# badge-inner1-revA.net
KiCad netlist of a schematic drawn in EAGLE
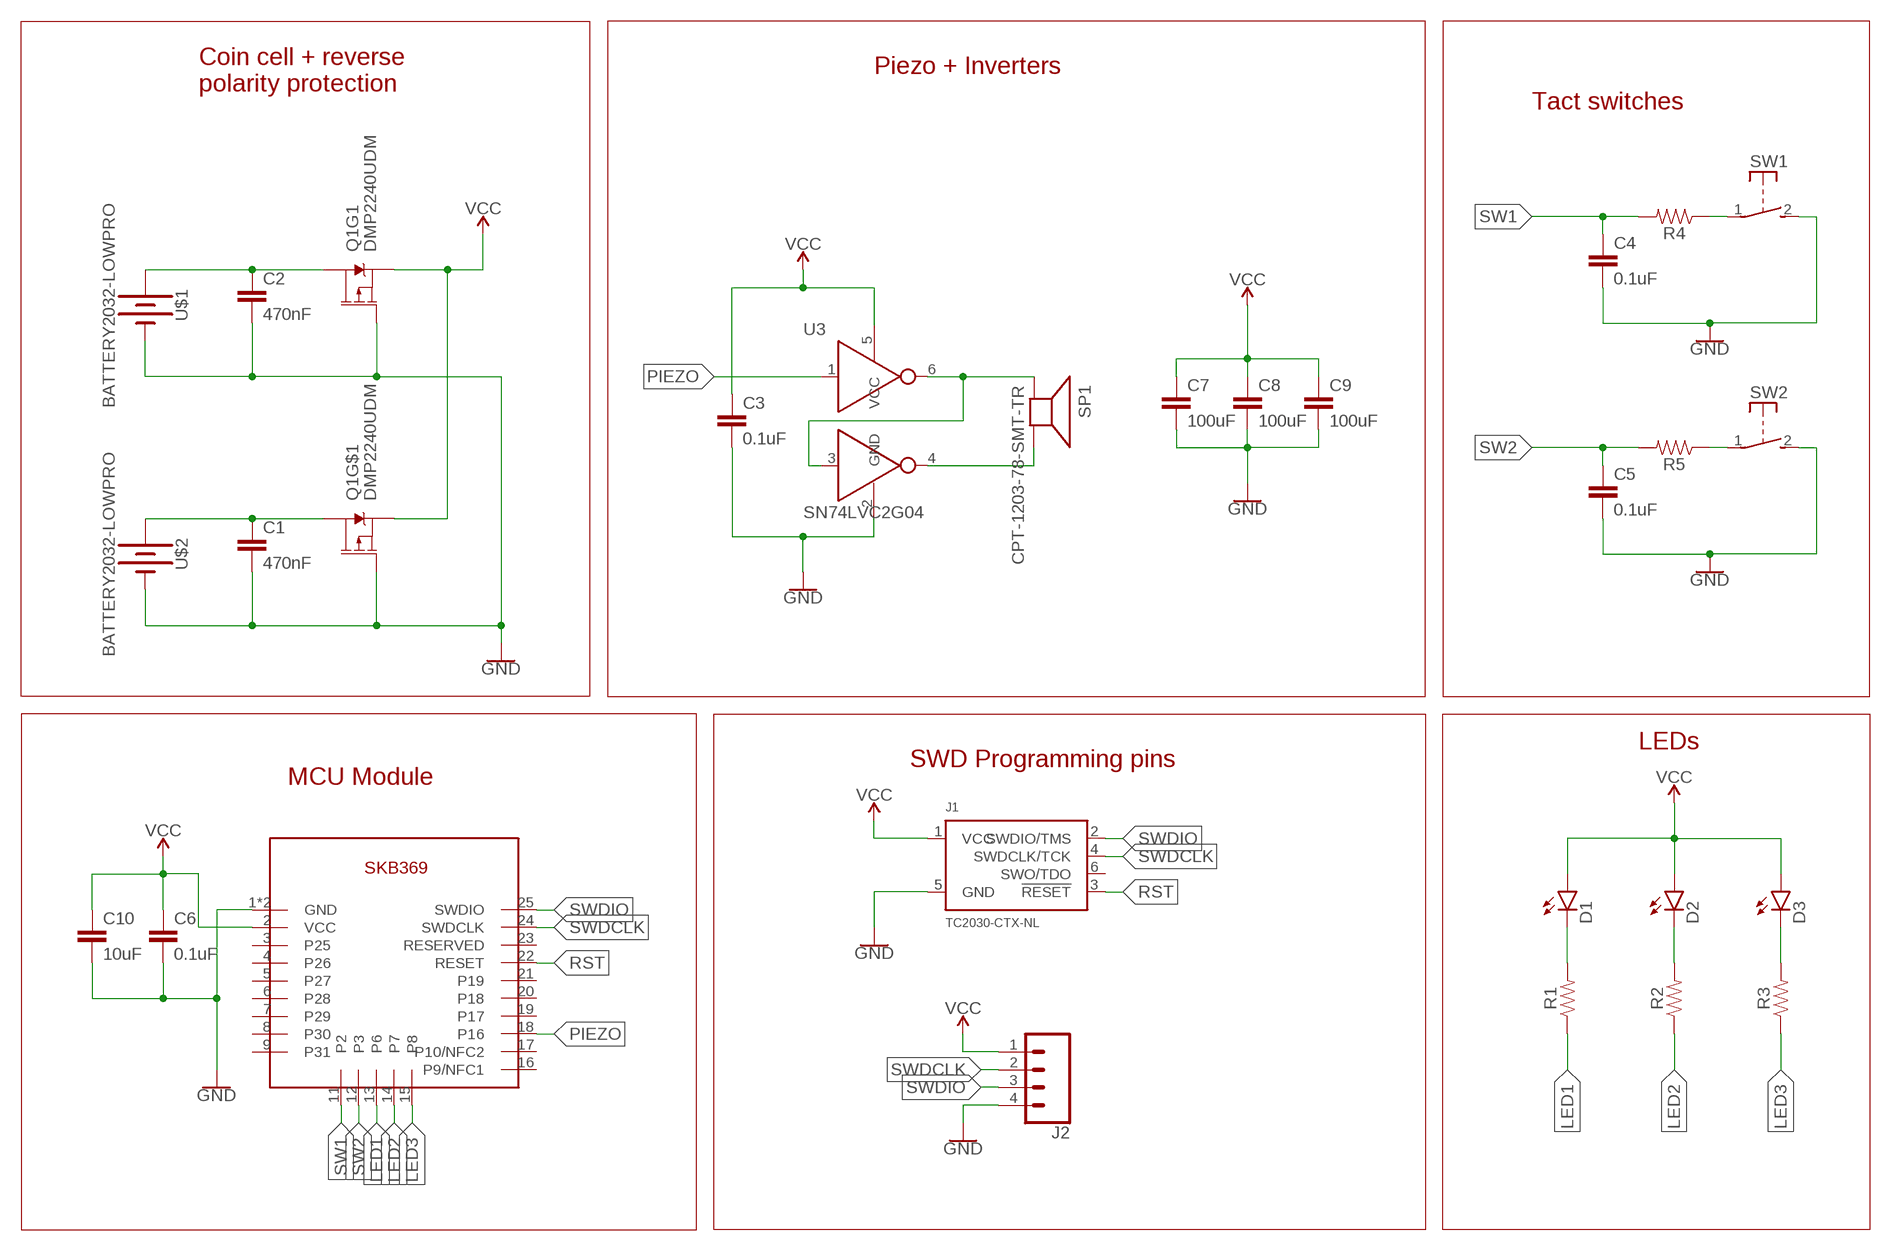
[diagram p0: schematic, sheet 1]

(export (version "E")
  (design (tool "Eeschema 10.0.6"))
  (components
    (comp (ref "C1")
      (value "470nF")
      (footprint "eagle-import:0603")
      (libsource (lib "eagle-import") (part "0.1UF-0603-25V-5%"))
    )
    (comp (ref "C2")
      (value "470nF")
      (footprint "eagle-import:0603")
      (libsource (lib "eagle-import") (part "0.1UF-0603-25V-5%"))
    )
    (comp (ref "C3")
      (value "0.1uF")
      (footprint "eagle-import:0603")
      (libsource (lib "eagle-import") (part "0.1UF-0603-25V-5%"))
    )
    (comp (ref "C4")
      (value "0.1uF")
      (footprint "eagle-import:0603")
      (libsource (lib "eagle-import") (part "0.1UF-0603-25V-5%"))
    )
    (comp (ref "C5")
      (value "0.1uF")
      (footprint "eagle-import:0603")
      (libsource (lib "eagle-import") (part "0.1UF-0603-25V-5%"))
    )
    (comp (ref "C6")
      (value "0.1uF")
      (footprint "eagle-import:0603")
      (libsource (lib "eagle-import") (part "0.1UF-0603-25V-5%"))
    )
    (comp (ref "C7")
      (value "100uF")
      (footprint "eagle-import:1206")
      (fields (field (name "SPICEPREFIX") "C"))
      (libsource (lib "eagle-import") (part "10UF-1206-6.3V-20%"))
    )
    (comp (ref "C8")
      (value "100uF")
      (footprint "eagle-import:1206")
      (fields (field (name "SPICEPREFIX") "C"))
      (libsource (lib "eagle-import") (part "10UF-1206-6.3V-20%"))
    )
    (comp (ref "C9")
      (value "100uF")
      (footprint "eagle-import:1206")
      (fields (field (name "SPICEPREFIX") "C"))
      (libsource (lib "eagle-import") (part "10UF-1206-6.3V-20%"))
    )
    (comp (ref "C10")
      (value "10uF")
      (footprint "eagle-import:0603")
      (libsource (lib "eagle-import") (part "0.1UF-0603-25V-5%"))
    )
    (comp (ref "D1")
      (value "SIDE-LED")
      (footprint "eagle-import:SIDE-LED")
      (libsource (lib "eagle-import") (part "SIDE-LED"))
    )
    (comp (ref "D2")
      (value "SIDE-LED")
      (footprint "eagle-import:SIDE-LED")
      (libsource (lib "eagle-import") (part "SIDE-LED"))
    )
    (comp (ref "D3")
      (value "SIDE-LED")
      (footprint "eagle-import:SIDE-LED")
      (libsource (lib "eagle-import") (part "SIDE-LED"))
    )
    (comp (ref "J1")
      (value "TC2030-CTX-NL")
      (footprint "eagle-import:TC2030-IDC-NL")
      (fields (field (name "MF") "Tag-Connect LLC") (field (name "MP") "TC2030-CTX"))
      (libsource (lib "eagle-import") (part "TC2030-CTX-NL"))
    )
    (comp (ref "J2")
      (value "CONN_04SMD_RA_FEMALE")
      (footprint "eagle-import:1X04_SMD_RA_FEMALE")
      (libsource (lib "eagle-import") (part "CONN_04SMD_RA_FEMALE"))
    )
    (comp (ref "Q1")
      (value "DMP2240UDM")
      (footprint "eagle-import:SOT26")
      (libsource (lib "eagle-import") (part "MOSFET_PCH_DUAL-DMP2240UDM"))
    )
    (comp (ref "R1")
      (value "0.05OHM-0603-1/5W-1%")
      (footprint "eagle-import:0603")
      (libsource (lib "eagle-import") (part "0.05OHM-0603-1/5W-1%"))
    )
    (comp (ref "R2")
      (value "0.05OHM-0603-1/5W-1%")
      (footprint "eagle-import:0603")
      (libsource (lib "eagle-import") (part "0.05OHM-0603-1/5W-1%"))
    )
    (comp (ref "R3")
      (value "0.05OHM-0603-1/5W-1%")
      (footprint "eagle-import:0603")
      (libsource (lib "eagle-import") (part "0.05OHM-0603-1/5W-1%"))
    )
    (comp (ref "R4")
      (value "0.05OHM-0603-1/5W-1%")
      (footprint "eagle-import:0603")
      (libsource (lib "eagle-import") (part "0.05OHM-0603-1/5W-1%"))
    )
    (comp (ref "R5")
      (value "0.05OHM-0603-1/5W-1%")
      (footprint "eagle-import:0603")
      (libsource (lib "eagle-import") (part "0.05OHM-0603-1/5W-1%"))
    )
    (comp (ref "SP1")
      (value "CPT-1203-78-SMT-TR")
      (footprint "eagle-import:CPT-1203-78-SMT-TR")
      (libsource (lib "eagle-import") (part "SPEAKER"))
    )
    (comp (ref "SW1")
      (value "EVQP4")
      (footprint "eagle-import:EVQP4KB")
      (libsource (lib "eagle-import") (part "EVQP4"))
    )
    (comp (ref "SW2")
      (value "EVQP4")
      (footprint "eagle-import:EVQP4KB")
      (libsource (lib "eagle-import") (part "EVQP4"))
    )
    (comp (ref "U$1")
      (value "BATTERY2032-LOWPRO")
      (footprint "eagle-import:COINCELL20LOWPRO")
      (libsource (lib "eagle-import") (part "BATTERY2032-LOWPRO"))
    )
    (comp (ref "U$2")
      (value "BATTERY2032-LOWPRO")
      (footprint "eagle-import:COINCELL20LOWPRO")
      (libsource (lib "eagle-import") (part "BATTERY2032-LOWPRO"))
    )
    (comp (ref "U1")
      (value "SKB369")
      (footprint "eagle-import:SKB369")
      (libsource (lib "eagle-import") (part "SKB369"))
    )
    (comp (ref "U3")
      (value "SN74LVC2G04")
      (footprint "eagle-import:SC70")
      (libsource (lib "eagle-import") (part "DUAL-INVERTERSN74LVC2G04"))
    )
  )
  (nets
    (net (code "1") (name "GND") (class "Default")
      (node (ref "C1") (pin "2") (pinfunction "2_2") (pintype "passive"))
      (node (ref "C10") (pin "2") (pinfunction "2_2") (pintype "passive"))
      (node (ref "C2") (pin "2") (pinfunction "2_2") (pintype "passive"))
      (node (ref "C3") (pin "2") (pinfunction "2_2") (pintype "passive"))
      (node (ref "C4") (pin "2") (pinfunction "2_2") (pintype "passive"))
      (node (ref "C5") (pin "2") (pinfunction "2_2") (pintype "passive"))
      (node (ref "C6") (pin "2") (pinfunction "2_2") (pintype "passive"))
      (node (ref "C7") (pin "2") (pinfunction "2_2") (pintype "passive"))
      (node (ref "C8") (pin "2") (pinfunction "2_2") (pintype "passive"))
      (node (ref "C9") (pin "2") (pinfunction "2_2") (pintype "passive"))
      (node (ref "J1") (pin "5") (pinfunction "GND_5") (pintype "bidirectional"))
      (node (ref "J2") (pin "4") (pinfunction "4_4") (pintype "passive"))
      (node (ref "Q1") (pin "G1") (pinfunction "G_G1") (pintype "bidirectional"))
      (node (ref "Q1") (pin "G2") (pinfunction "G_G2") (pintype "bidirectional"))
      (node (ref "SW1") (pin "2") (pinfunction "S_2") (pintype "passive"))
      (node (ref "SW2") (pin "2") (pinfunction "S_2") (pintype "passive"))
      (node (ref "U$1") (pin "P$2") (pinfunction "-_P$2") (pintype "power_in"))
      (node (ref "U$2") (pin "P$2") (pinfunction "-_P$2") (pintype "power_in"))
      (node (ref "U1") (pin "1") (pinfunction "GND_1") (pintype "bidirectional"))
      (node (ref "U1") (pin "10") (pinfunction "GND_10") (pintype "bidirectional"))
      (node (ref "U3") (pin "2") (pinfunction "GND_2") (pintype "bidirectional"))
    )
    (net (code "2") (name "LED1") (class "Default")
      (node (ref "R1") (pin "1") (pinfunction "1_1") (pintype "passive"))
      (node (ref "U1") (pin "13") (pinfunction "P6_13") (pintype "bidirectional"))
    )
    (net (code "3") (name "LED2") (class "Default")
      (node (ref "R2") (pin "1") (pinfunction "1_1") (pintype "passive"))
      (node (ref "U1") (pin "14") (pinfunction "P7_14") (pintype "bidirectional"))
    )
    (net (code "4") (name "LED3") (class "Default")
      (node (ref "R3") (pin "1") (pinfunction "1_1") (pintype "passive"))
      (node (ref "U1") (pin "15") (pinfunction "P8_15") (pintype "bidirectional"))
    )
    (net (code "5") (name "Net-(D1-C)") (class "Default")
      (node (ref "D1") (pin "1") (pinfunction "C_1") (pintype "passive"))
      (node (ref "R1") (pin "2") (pinfunction "2_2") (pintype "passive"))
    )
    (net (code "6") (name "Net-(D2-C)") (class "Default")
      (node (ref "D2") (pin "1") (pinfunction "C_1") (pintype "passive"))
      (node (ref "R2") (pin "2") (pinfunction "2_2") (pintype "passive"))
    )
    (net (code "7") (name "Net-(D3-C)") (class "Default")
      (node (ref "D3") (pin "1") (pinfunction "C_1") (pintype "passive"))
      (node (ref "R3") (pin "2") (pinfunction "2_2") (pintype "passive"))
    )
    (net (code "8") (name "Net-(Q1A-D)") (class "Default")
      (node (ref "C1") (pin "1") (pinfunction "1_1") (pintype "passive"))
      (node (ref "Q1") (pin "D2") (pinfunction "D_D2") (pintype "bidirectional"))
      (node (ref "U$2") (pin "P$1") (pinfunction "+_P$1") (pintype "power_in"))
    )
    (net (code "9") (name "Net-(Q1B-D)") (class "Default")
      (node (ref "C2") (pin "1") (pinfunction "1_1") (pintype "passive"))
      (node (ref "Q1") (pin "D1") (pinfunction "D_D1") (pintype "bidirectional"))
      (node (ref "U$1") (pin "P$1") (pinfunction "+_P$1") (pintype "power_in"))
    )
    (net (code "10") (name "Net-(SP1-+)") (class "Default")
      (node (ref "SP1") (pin "P$1") (pinfunction "+_P$1") (pintype "passive"))
      (node (ref "U3") (pin "3") (pinfunction "A2_3") (pintype "bidirectional"))
      (node (ref "U3") (pin "6") (pinfunction "Y1_6") (pintype "bidirectional"))
    )
    (net (code "11") (name "Net-(SP1--)") (class "Default")
      (node (ref "SP1") (pin "P$2") (pinfunction "-_P$2") (pintype "passive"))
      (node (ref "U3") (pin "4") (pinfunction "Y2_4") (pintype "bidirectional"))
    )
    (net (code "12") (name "Net-(SW1-P)") (class "Default")
      (node (ref "R4") (pin "1") (pinfunction "1_1") (pintype "passive"))
      (node (ref "SW1") (pin "1") (pinfunction "P_1") (pintype "passive"))
    )
    (net (code "13") (name "Net-(SW2-P)") (class "Default")
      (node (ref "R5") (pin "1") (pinfunction "1_1") (pintype "passive"))
      (node (ref "SW2") (pin "1") (pinfunction "P_1") (pintype "passive"))
    )
    (net (code "14") (name "PIEZO") (class "Default")
      (node (ref "U1") (pin "18") (pinfunction "P16_18") (pintype "bidirectional"))
      (node (ref "U3") (pin "1") (pinfunction "A1_1") (pintype "bidirectional"))
    )
    (net (code "15") (name "RST") (class "Default")
      (node (ref "J1") (pin "3") (pinfunction "~{RESET}_3") (pintype "bidirectional"))
      (node (ref "U1") (pin "22") (pinfunction "RESET_22") (pintype "bidirectional"))
    )
    (net (code "16") (name "SW1") (class "Default")
      (node (ref "C4") (pin "1") (pinfunction "1_1") (pintype "passive"))
      (node (ref "R4") (pin "2") (pinfunction "2_2") (pintype "passive"))
      (node (ref "U1") (pin "11") (pinfunction "P2_11") (pintype "bidirectional"))
    )
    (net (code "17") (name "SW2") (class "Default")
      (node (ref "C5") (pin "1") (pinfunction "1_1") (pintype "passive"))
      (node (ref "R5") (pin "2") (pinfunction "2_2") (pintype "passive"))
      (node (ref "U1") (pin "12") (pinfunction "P3_12") (pintype "bidirectional"))
    )
    (net (code "18") (name "SWDCLK") (class "Default")
      (node (ref "J1") (pin "4") (pinfunction "SWDCLK/TCK_4") (pintype "bidirectional"))
      (node (ref "J2") (pin "2") (pinfunction "2_2") (pintype "passive"))
      (node (ref "U1") (pin "24") (pinfunction "SWDCLK_24") (pintype "bidirectional"))
    )
    (net (code "19") (name "SWDIO") (class "Default")
      (node (ref "J1") (pin "2") (pinfunction "SWDIO/TMS_2") (pintype "bidirectional"))
      (node (ref "J2") (pin "3") (pinfunction "3_3") (pintype "passive"))
      (node (ref "U1") (pin "25") (pinfunction "SWDIO_25") (pintype "bidirectional"))
    )
    (net (code "20") (name "VCC") (class "Default")
      (node (ref "C10") (pin "1") (pinfunction "1_1") (pintype "passive"))
      (node (ref "C3") (pin "1") (pinfunction "1_1") (pintype "passive"))
      (node (ref "C6") (pin "1") (pinfunction "1_1") (pintype "passive"))
      (node (ref "C7") (pin "1") (pinfunction "1_1") (pintype "passive"))
      (node (ref "C8") (pin "1") (pinfunction "1_1") (pintype "passive"))
      (node (ref "C9") (pin "1") (pinfunction "1_1") (pintype "passive"))
      (node (ref "D1") (pin "2") (pinfunction "A_2") (pintype "passive"))
      (node (ref "D2") (pin "2") (pinfunction "A_2") (pintype "passive"))
      (node (ref "D3") (pin "2") (pinfunction "A_2") (pintype "passive"))
      (node (ref "J1") (pin "1") (pinfunction "VCC_1") (pintype "bidirectional"))
      (node (ref "J2") (pin "1") (pinfunction "1_1") (pintype "passive"))
      (node (ref "Q1") (pin "S1") (pinfunction "S_S1") (pintype "bidirectional"))
      (node (ref "Q1") (pin "S2") (pinfunction "S_S2") (pintype "bidirectional"))
      (node (ref "U1") (pin "2") (pinfunction "VCC_2") (pintype "bidirectional"))
      (node (ref "U3") (pin "5") (pinfunction "VCC_5") (pintype "bidirectional"))
    )
    (net (code "21") (name "unconnected-(J1-SWO{slash}TDO-Pad6)") (class "Default")
      (node (ref "J1") (pin "6") (pinfunction "SWO/TDO_6") (pintype "bidirectional"))
    )
    (net (code "22") (name "unconnected-(U1-P9{slash}NFC1-Pad16)") (class "Default")
      (node (ref "U1") (pin "16") (pinfunction "P9/NFC1_16") (pintype "bidirectional"))
    )
    (net (code "23") (name "unconnected-(U1-P10{slash}NFC2-Pad17)") (class "Default")
      (node (ref "U1") (pin "17") (pinfunction "P10/NFC2_17") (pintype "bidirectional"))
    )
    (net (code "24") (name "unconnected-(U1-P17-Pad19)") (class "Default")
      (node (ref "U1") (pin "19") (pinfunction "P17_19") (pintype "bidirectional"))
    )
    (net (code "25") (name "unconnected-(U1-P18-Pad20)") (class "Default")
      (node (ref "U1") (pin "20") (pinfunction "P18_20") (pintype "bidirectional"))
    )
    (net (code "26") (name "unconnected-(U1-P19-Pad21)") (class "Default")
      (node (ref "U1") (pin "21") (pinfunction "P19_21") (pintype "bidirectional"))
    )
    (net (code "27") (name "unconnected-(U1-P25-Pad3)") (class "Default")
      (node (ref "U1") (pin "3") (pinfunction "P25_3") (pintype "bidirectional"))
    )
    (net (code "28") (name "unconnected-(U1-P26-Pad4)") (class "Default")
      (node (ref "U1") (pin "4") (pinfunction "P26_4") (pintype "bidirectional"))
    )
    (net (code "29") (name "unconnected-(U1-P27-Pad5)") (class "Default")
      (node (ref "U1") (pin "5") (pinfunction "P27_5") (pintype "bidirectional"))
    )
    (net (code "30") (name "unconnected-(U1-P28-Pad6)") (class "Default")
      (node (ref "U1") (pin "6") (pinfunction "P28_6") (pintype "bidirectional"))
    )
    (net (code "31") (name "unconnected-(U1-P29-Pad7)") (class "Default")
      (node (ref "U1") (pin "7") (pinfunction "P29_7") (pintype "bidirectional"))
    )
    (net (code "32") (name "unconnected-(U1-P30-Pad8)") (class "Default")
      (node (ref "U1") (pin "8") (pinfunction "P30_8") (pintype "bidirectional"))
    )
    (net (code "33") (name "unconnected-(U1-P31-Pad9)") (class "Default")
      (node (ref "U1") (pin "9") (pinfunction "P31_9") (pintype "bidirectional"))
    )
    (net (code "34") (name "unconnected-(U1-RESERVED-Pad23)") (class "Default")
      (node (ref "U1") (pin "23") (pinfunction "RESERVED_23") (pintype "bidirectional"))
    )
  )
)
